# eye.net
KiCad netlist of a schematic drawn in Altium Designer
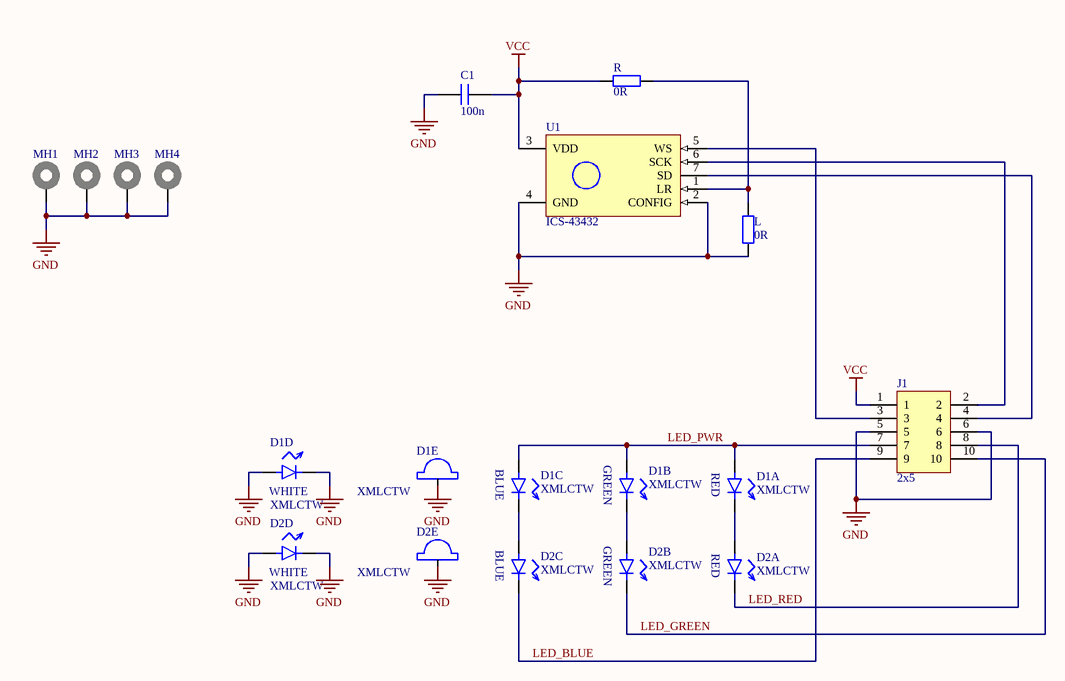
[diagram p0: eye.SchDoc]

(export (version "E")
  (design (tool "Eeschema 10.0.6"))
  (components
    (comp (ref "C1")
      (value "100n")
      (footprint "CAPC1005X06N")
      (description "Capacitor")
      (fields (field (name "Comment") "cap"))
      (libsource (lib "lib_passives") (part "cap"))
    )
    (comp (ref "D1")
      (value "XMLCTW")
      (footprint "PSON125P500X302_HS-9N")
      (libsource (lib "lib_cree") (part "xmlctw"))
    )
    (comp (ref "D2")
      (value "XMLCTW")
      (footprint "PSON125P500X302_HS-9N")
      (libsource (lib "lib_cree") (part "xmlctw"))
    )
    (comp (ref "J1")
      (value "2x5")
      (footprint "hdr_2x5_50mil")
      (description "2x5 Header")
      (libsource (lib "lib_connectors") (part "hdr_2x5"))
    )
    (comp (ref "L")
      (value "0R")
      (footprint "RESC1005X04N")
      (description "Resistor")
      (fields (field (name "Comment") "res"))
      (libsource (lib "") (part "res_1"))
    )
    (comp (ref "MH1")
      (value "ID2.25x2.5mm")
      (footprint "9774025943")
      (description "WA-SMST SMT Steel Spacer non stop, OD4.35mm, ID2.25x2.5mm")
      (fields (field (name "PART NUMBER") "9774025943R") (field (name "PUBLISHER") "Wurth Elektronik"))
      (libsource (lib "Altium_SMST (rev19b)") (part "9774025943R"))
    )
    (comp (ref "MH2")
      (value "ID2.25x2.5mm")
      (footprint "9774025943")
      (description "WA-SMST SMT Steel Spacer non stop, OD4.35mm, ID2.25x2.5mm")
      (fields (field (name "PART NUMBER") "9774025943R") (field (name "PUBLISHER") "Wurth Elektronik"))
      (libsource (lib "Altium_SMST (rev19b)") (part "9774025943R"))
    )
    (comp (ref "MH3")
      (value "ID2.25x2.5mm")
      (footprint "9774025943")
      (description "WA-SMST SMT Steel Spacer non stop, OD4.35mm, ID2.25x2.5mm")
      (fields (field (name "PART NUMBER") "9774025943R") (field (name "PUBLISHER") "Wurth Elektronik"))
      (libsource (lib "Altium_SMST (rev19b)") (part "9774025943R"))
    )
    (comp (ref "MH4")
      (value "ID2.25x2.5mm")
      (footprint "9774025943")
      (description "WA-SMST SMT Steel Spacer non stop, OD4.35mm, ID2.25x2.5mm")
      (fields (field (name "PART NUMBER") "9774025943R") (field (name "PUBLISHER") "Wurth Elektronik"))
      (libsource (lib "Altium_SMST (rev19b)") (part "9774025943R"))
    )
    (comp (ref "R")
      (value "0R")
      (footprint "RESC1005X04N")
      (description "Resistor")
      (fields (field (name "Comment") "res"))
      (libsource (lib "lib_passives") (part "res"))
    )
    (comp (ref "U1")
      (value "ICS-43432")
      (footprint "PSON65P300X110-6N")
      (libsource (lib "lib_invensense") (part "ics-43432"))
    )
  )
  (nets
    (net (code "1") (name "/LED_BLUE") (class "Default")
      (node (ref "D2") (pin "BC") (pinfunction "BC_BC") (pintype "passive"))
      (node (ref "J1") (pin "9") (pinfunction "9_9") (pintype "passive"))
    )
    (net (code "2") (name "/LED_GREEN") (class "Default")
      (node (ref "D2") (pin "GC") (pinfunction "GC_GC") (pintype "passive"))
      (node (ref "J1") (pin "10") (pinfunction "10_10") (pintype "passive"))
    )
    (net (code "3") (name "/LED_PWR") (class "Default")
      (node (ref "D1") (pin "BA") (pinfunction "BA_BA") (pintype "passive"))
      (node (ref "D1") (pin "GA") (pinfunction "GA_GA") (pintype "passive"))
      (node (ref "D1") (pin "RA") (pinfunction "RA_RA") (pintype "passive"))
      (node (ref "J1") (pin "7") (pinfunction "7_7") (pintype "passive"))
    )
    (net (code "4") (name "/LED_RED") (class "Default")
      (node (ref "D2") (pin "RC") (pinfunction "RC_RC") (pintype "passive"))
      (node (ref "J1") (pin "8") (pinfunction "8_8") (pintype "passive"))
    )
    (net (code "5") (name "GND") (class "Default")
      (node (ref "C1") (pin "1") (pinfunction "1_1") (pintype "passive"))
      (node (ref "D1") (pin "9") (pinfunction "PAD_9") (pintype "passive"))
      (node (ref "D1") (pin "WA") (pinfunction "WA_WA") (pintype "passive"))
      (node (ref "D1") (pin "WC") (pinfunction "WC_WC") (pintype "passive"))
      (node (ref "D2") (pin "9") (pinfunction "PAD_9") (pintype "passive"))
      (node (ref "D2") (pin "WA") (pinfunction "WA_WA") (pintype "passive"))
      (node (ref "D2") (pin "WC") (pinfunction "WC_WC") (pintype "passive"))
      (node (ref "J1") (pin "5") (pinfunction "5_5") (pintype "passive"))
      (node (ref "J1") (pin "6") (pinfunction "6_6") (pintype "passive"))
      (node (ref "L") (pin "1") (pinfunction "1_1") (pintype "passive"))
      (node (ref "MH1") (pin "1") (pinfunction "1_1") (pintype "passive"))
      (node (ref "MH2") (pin "1") (pinfunction "1_1") (pintype "passive"))
      (node (ref "MH3") (pin "1") (pinfunction "1_1") (pintype "passive"))
      (node (ref "MH4") (pin "1") (pinfunction "1_1") (pintype "passive"))
      (node (ref "U1") (pin "2") (pinfunction "CONFIG_2") (pintype "input"))
      (node (ref "U1") (pin "4") (pinfunction "GND_4") (pintype "power_in"))
    )
    (net (code "6") (name "Net-(D1-PadBC)") (class "Default")
      (node (ref "D1") (pin "BC") (pinfunction "BC_BC") (pintype "passive"))
      (node (ref "D2") (pin "BA") (pinfunction "BA_BA") (pintype "passive"))
    )
    (net (code "7") (name "Net-(D1-PadGC)") (class "Default")
      (node (ref "D1") (pin "GC") (pinfunction "GC_GC") (pintype "passive"))
      (node (ref "D2") (pin "GA") (pinfunction "GA_GA") (pintype "passive"))
    )
    (net (code "8") (name "Net-(D1-PadRC)") (class "Default")
      (node (ref "D1") (pin "RC") (pinfunction "RC_RC") (pintype "passive"))
      (node (ref "D2") (pin "RA") (pinfunction "RA_RA") (pintype "passive"))
    )
    (net (code "9") (name "Net-(U1-LR)") (class "Default")
      (node (ref "L") (pin "2") (pinfunction "2_2") (pintype "passive"))
      (node (ref "R") (pin "1") (pinfunction "1_1") (pintype "passive"))
      (node (ref "U1") (pin "1") (pinfunction "LR_1") (pintype "input"))
    )
    (net (code "10") (name "Net-(U1-SCK)") (class "Default")
      (node (ref "J1") (pin "2") (pinfunction "2_2") (pintype "passive"))
      (node (ref "U1") (pin "6") (pinfunction "SCK_6") (pintype "input"))
    )
    (net (code "11") (name "Net-(U1-SD)") (class "Default")
      (node (ref "J1") (pin "4") (pinfunction "4_4") (pintype "passive"))
      (node (ref "U1") (pin "7") (pinfunction "SD_7") (pintype "open_collector"))
    )
    (net (code "12") (name "Net-(U1-WS)") (class "Default")
      (node (ref "J1") (pin "3") (pinfunction "3_3") (pintype "passive"))
      (node (ref "U1") (pin "5") (pinfunction "WS_5") (pintype "input"))
    )
    (net (code "13") (name "VCC") (class "Default")
      (node (ref "C1") (pin "2") (pinfunction "2_2") (pintype "passive"))
      (node (ref "J1") (pin "1") (pinfunction "1_1") (pintype "passive"))
      (node (ref "R") (pin "2") (pinfunction "2_2") (pintype "passive"))
      (node (ref "U1") (pin "3") (pinfunction "VDD_3") (pintype "power_in"))
    )
  )
)
